# AudioAmp.net
KiCad netlist of a schematic drawn in Altium Designer
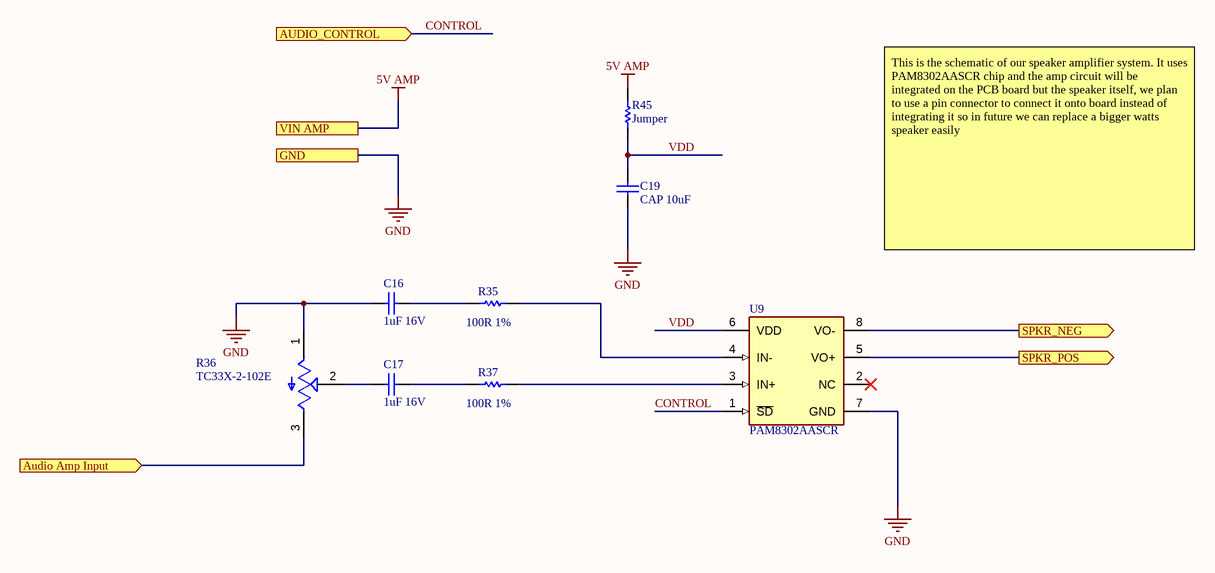
[diagram p0: AudioAmp.SchDoc]

(export (version "E")
  (design (tool "Eeschema 10.0.6"))
  (components
    (comp (ref "C16")
      (value "1uF 16V")
      (footprint "CAPC0603(1608)100_N")
      (description "CAP 1uF 16V ±5% 0603 (1608 Metric) Thickness 1mm SMD")
      (fields (field (name "TOLERANCE") "Â±5%"))
      (libsource (lib "Altium Content Vault") (part "CAP"))
    )
    (comp (ref "C17")
      (value "1uF 16V")
      (footprint "CAPC0603(1608)100_N")
      (description "CAP 1uF 16V ±5% 0603 (1608 Metric) Thickness 1mm SMD")
      (fields (field (name "TOLERANCE") "Â±5%"))
      (libsource (lib "Altium Content Vault") (part "CAP"))
    )
    (comp (ref "C19")
      (value "CAP 10uF")
      (footprint "CAPC0805(2012)145_N")
      (description "CAP 10uF 16V ±10% 0805 (2012 Metric) Thickness 1.45mm SMD")
      (fields (field (name "TOLERANCE") "Â±10%"))
      (libsource (lib "Altium Content Vault") (part "CAP"))
    )
    (comp (ref "R35")
      (value "100R 1%")
      (footprint "RESC0603(1608)_M")
      (description "100R 0.1W 1% 0603 (1608 Metric)  SMD")
      (fields (field (name "TOLERANCE") "1 %") (field (name "POWER") "0.1 W"))
      (libsource (lib "Altium Content Vault") (part "RES"))
    )
    (comp (ref "R36")
      (value "TC33X-2-102E")
      (footprint "TRIM_TC33X-2-102E")
      (description "1 kOhms 0.1W, 1/10W J Lead Surface Mount Trimmer Potentiometer Cermet 1 Turn Top Adjustment")
      (fields (field (name "DIGI-KEY_PART_NUMBER") "TC33X-102ECT-ND") (field (name "MF") "Bourns"))
      (libsource (lib "TC33X-2-102E") (part "TC33X-2-102E"))
    )
    (comp (ref "R37")
      (value "100R 1%")
      (footprint "RESC0603(1608)_M")
      (description "100R 0.1W 1% 0603 (1608 Metric)  SMD")
      (fields (field (name "TOLERANCE") "1 %") (field (name "POWER") "0.1 W"))
      (libsource (lib "Altium Content Vault") (part "RES"))
    )
    (comp (ref "R45")
      (value "Jumper")
      (footprint "RESC0603(1608)_N")
      (description "Jumper 0603 (1608 Metric)")
      (fields (field (name "POWER") "None"))
      (libsource (lib "Altium Content Vault") (part "RES"))
    )
    (comp (ref "U9")
      (value "PAM8302AASCR")
      (footprint "FP-MSOP-8-MFG")
      (description "IC AMP CLASS D MONO 2.5W 8MSOP")
      (fields
        (field (name "MANUFACTURER") "Diodes Inc.")
        (field (name "OCTOPART") "https://octopart.com/pam8302aascr-diodes+inc.-29030473")
      )
      (libsource (lib "Altium Content Vault") (part "918354b19a62d7b7ebf36b39aeda0fe"))
    )
  )
  (nets
    (net (code "1") (name "/Audio Amp Input") (class "Default")
      (node (ref "R36") (pin "3") (pinfunction "CW_3") (pintype "passive"))
    )
    (net (code "2") (name "/CONTROL") (class "Default")
      (node (ref "U9") (pin "1") (pinfunction "~{SD}_1") (pintype "input"))
    )
    (net (code "3") (name "/SPKR_NEG") (class "Default")
      (node (ref "U9") (pin "8") (pinfunction "VO-_8") (pintype "power_in"))
    )
    (net (code "4") (name "/SPKR_POS") (class "Default")
      (node (ref "U9") (pin "5") (pinfunction "VO+_5") (pintype "power_in"))
    )
    (net (code "5") (name "/VDD") (class "Default")
      (node (ref "C19") (pin "2") (pinfunction "2_2") (pintype "passive"))
      (node (ref "R45") (pin "1") (pinfunction "1_1") (pintype "passive"))
      (node (ref "U9") (pin "6") (pinfunction "VDD_6") (pintype "power_in"))
    )
    (net (code "6") (name "5V AMP") (class "Default")
      (node (ref "R45") (pin "2") (pinfunction "2_2") (pintype "passive"))
    )
    (net (code "7") (name "GND") (class "Default")
      (node (ref "C16") (pin "2") (pinfunction "2_2") (pintype "passive"))
      (node (ref "C19") (pin "1") (pinfunction "1_1") (pintype "passive"))
      (node (ref "R36") (pin "1") (pinfunction "CCW_1") (pintype "passive"))
      (node (ref "U9") (pin "7") (pinfunction "GND_7") (pintype "power_in"))
    )
    (net (code "8") (name "Net-(C16-Pad1)") (class "Default")
      (node (ref "C16") (pin "1") (pinfunction "1_1") (pintype "passive"))
      (node (ref "R35") (pin "1") (pinfunction "1_1") (pintype "passive"))
    )
    (net (code "9") (name "Net-(C17-Pad1)") (class "Default")
      (node (ref "C17") (pin "1") (pinfunction "1_1") (pintype "passive"))
      (node (ref "R37") (pin "1") (pinfunction "1_1") (pintype "passive"))
    )
    (net (code "10") (name "Net-(R36-W)") (class "Default")
      (node (ref "C17") (pin "2") (pinfunction "2_2") (pintype "passive"))
      (node (ref "R36") (pin "2") (pinfunction "W_2") (pintype "passive"))
    )
    (net (code "11") (name "Net-(U9-IN+)") (class "Default")
      (node (ref "R37") (pin "2") (pinfunction "2_2") (pintype "passive"))
      (node (ref "U9") (pin "3") (pinfunction "IN+_3") (pintype "input"))
    )
    (net (code "12") (name "Net-(U9-IN-)") (class "Default")
      (node (ref "R35") (pin "2") (pinfunction "2_2") (pintype "passive"))
      (node (ref "U9") (pin "4") (pinfunction "IN-_4") (pintype "input"))
    )
    (net (code "13") (name "unconnected-(U9-NC-Pad2)") (class "Default")
      (node (ref "U9") (pin "2") (pinfunction "NC_2") (pintype "passive+no_connect"))
    )
  )
)
